# Gamepad_IO.net
KiCad netlist of a schematic drawn in Altium Designer
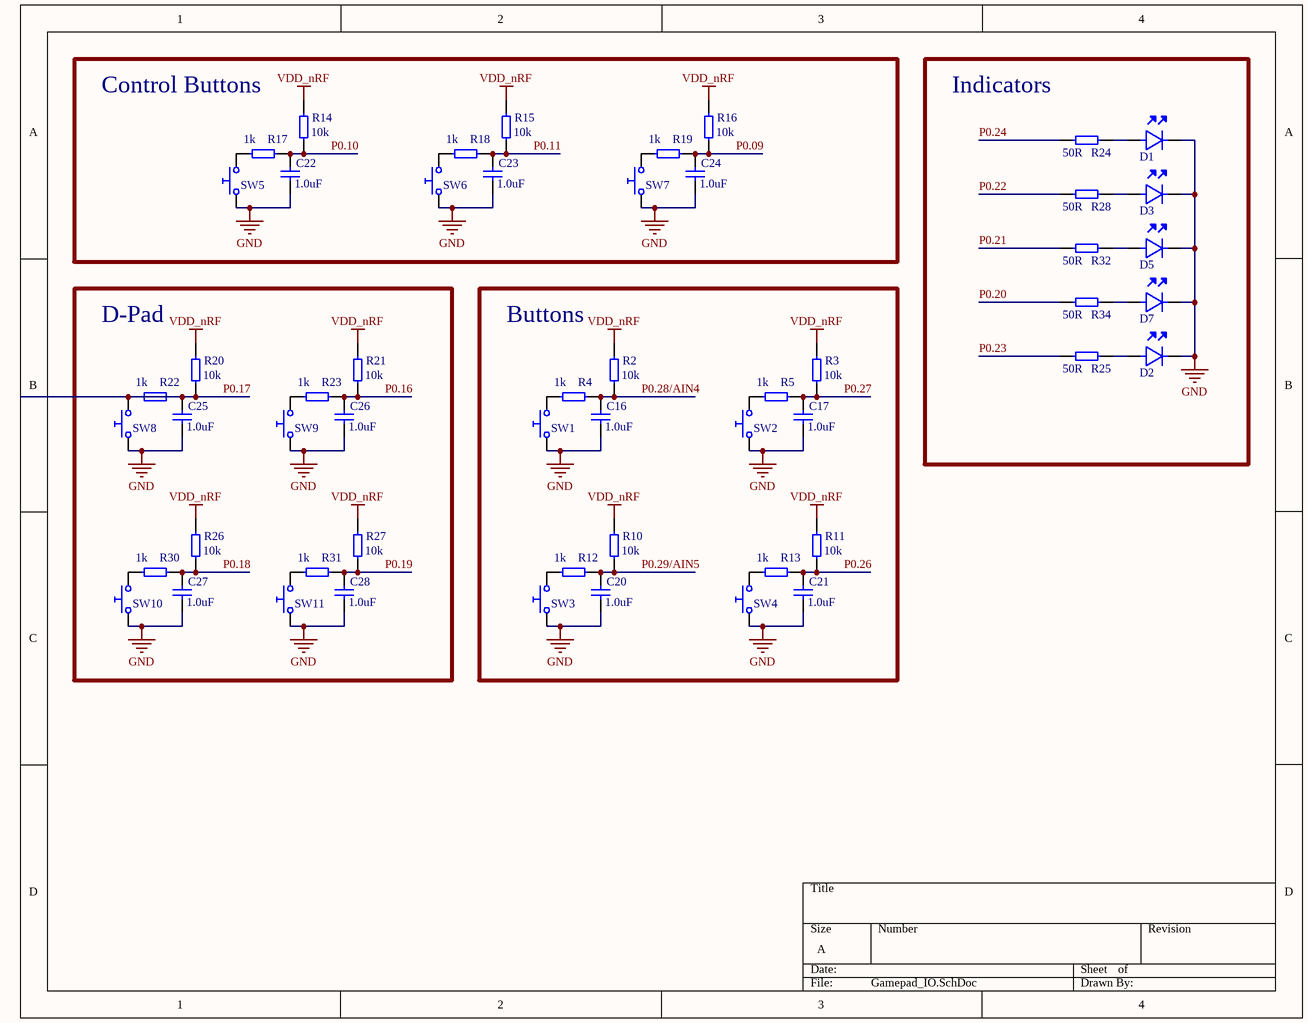
[diagram p0: Gamepad_IO.SchDoc]

(export (version "E")
  (design (tool "Eeschema 10.0.6"))
  (components
    (comp (ref "C16")
      (value "1.0uF")
      (footprint "0603 Capacitor")
      (libsource (lib "MoldsvorLibrary") (part "Capacitor"))
    )
    (comp (ref "C17")
      (value "1.0uF")
      (footprint "0603 Capacitor")
      (libsource (lib "MoldsvorLibrary") (part "Capacitor"))
    )
    (comp (ref "C20")
      (value "1.0uF")
      (footprint "0603 Capacitor")
      (libsource (lib "MoldsvorLibrary") (part "Capacitor"))
    )
    (comp (ref "C21")
      (value "1.0uF")
      (footprint "0603 Capacitor")
      (libsource (lib "MoldsvorLibrary") (part "Capacitor"))
    )
    (comp (ref "C22")
      (value "1.0uF")
      (footprint "0603 Capacitor")
      (libsource (lib "MoldsvorLibrary") (part "Capacitor"))
    )
    (comp (ref "C23")
      (value "1.0uF")
      (footprint "0603 Capacitor")
      (libsource (lib "MoldsvorLibrary") (part "Capacitor"))
    )
    (comp (ref "C24")
      (value "1.0uF")
      (footprint "0603 Capacitor")
      (libsource (lib "MoldsvorLibrary") (part "Capacitor"))
    )
    (comp (ref "C25")
      (value "1.0uF")
      (footprint "0603 Capacitor")
      (libsource (lib "MoldsvorLibrary") (part "Capacitor"))
    )
    (comp (ref "C26")
      (value "1.0uF")
      (footprint "0603 Capacitor")
      (libsource (lib "MoldsvorLibrary") (part "Capacitor"))
    )
    (comp (ref "C27")
      (value "1.0uF")
      (footprint "0603 Capacitor")
      (libsource (lib "MoldsvorLibrary") (part "Capacitor"))
    )
    (comp (ref "C28")
      (value "1.0uF")
      (footprint "0603 Capacitor")
      (libsource (lib "MoldsvorLibrary") (part "Capacitor"))
    )
    (comp (ref "D1") (value "LED") (footprint "0603 LED") (libsource (lib "MoldsvorLibrary") (part "LED")))
    (comp (ref "D2") (value "LED") (footprint "0603 LED") (libsource (lib "MoldsvorLibrary") (part "LED")))
    (comp (ref "D3") (value "LED") (footprint "0603 LED") (libsource (lib "MoldsvorLibrary") (part "LED")))
    (comp (ref "D5") (value "LED") (footprint "0603 LED") (libsource (lib "MoldsvorLibrary") (part "LED")))
    (comp (ref "D7") (value "LED") (footprint "0603 LED") (libsource (lib "MoldsvorLibrary") (part "LED")))
    (comp (ref "R2")
      (value "10k")
      (footprint "0603 Resistor")
      (libsource (lib "MoldsvorLibrary") (part "Resistor"))
    )
    (comp (ref "R3")
      (value "10k")
      (footprint "0603 Resistor")
      (libsource (lib "MoldsvorLibrary") (part "Resistor"))
    )
    (comp (ref "R4")
      (value "1k")
      (footprint "0603 Resistor")
      (libsource (lib "MoldsvorLibrary") (part "Resistor"))
    )
    (comp (ref "R5")
      (value "1k")
      (footprint "0603 Resistor")
      (libsource (lib "MoldsvorLibrary") (part "Resistor"))
    )
    (comp (ref "R10")
      (value "10k")
      (footprint "0603 Resistor")
      (libsource (lib "MoldsvorLibrary") (part "Resistor"))
    )
    (comp (ref "R11")
      (value "10k")
      (footprint "0603 Resistor")
      (libsource (lib "MoldsvorLibrary") (part "Resistor"))
    )
    (comp (ref "R12")
      (value "1k")
      (footprint "0603 Resistor")
      (libsource (lib "MoldsvorLibrary") (part "Resistor"))
    )
    (comp (ref "R13")
      (value "1k")
      (footprint "0603 Resistor")
      (libsource (lib "MoldsvorLibrary") (part "Resistor"))
    )
    (comp (ref "R14")
      (value "10k")
      (footprint "0603 Resistor")
      (libsource (lib "MoldsvorLibrary") (part "Resistor"))
    )
    (comp (ref "R15")
      (value "10k")
      (footprint "0603 Resistor")
      (libsource (lib "MoldsvorLibrary") (part "Resistor"))
    )
    (comp (ref "R16")
      (value "10k")
      (footprint "0603 Resistor")
      (libsource (lib "MoldsvorLibrary") (part "Resistor"))
    )
    (comp (ref "R17")
      (value "1k")
      (footprint "0603 Resistor")
      (libsource (lib "MoldsvorLibrary") (part "Resistor"))
    )
    (comp (ref "R18")
      (value "1k")
      (footprint "0603 Resistor")
      (libsource (lib "MoldsvorLibrary") (part "Resistor"))
    )
    (comp (ref "R19")
      (value "1k")
      (footprint "0603 Resistor")
      (libsource (lib "MoldsvorLibrary") (part "Resistor"))
    )
    (comp (ref "R20")
      (value "10k")
      (footprint "0603 Resistor")
      (libsource (lib "MoldsvorLibrary") (part "Resistor"))
    )
    (comp (ref "R21")
      (value "10k")
      (footprint "0603 Resistor")
      (libsource (lib "MoldsvorLibrary") (part "Resistor"))
    )
    (comp (ref "R22")
      (value "1k")
      (footprint "0603 Resistor")
      (libsource (lib "MoldsvorLibrary") (part "Resistor"))
    )
    (comp (ref "R23")
      (value "1k")
      (footprint "0603 Resistor")
      (libsource (lib "MoldsvorLibrary") (part "Resistor"))
    )
    (comp (ref "R24")
      (value "50R")
      (footprint "0603 Resistor")
      (libsource (lib "MoldsvorLibrary") (part "Resistor"))
    )
    (comp (ref "R25")
      (value "50R")
      (footprint "0603 Resistor")
      (libsource (lib "MoldsvorLibrary") (part "Resistor"))
    )
    (comp (ref "R26")
      (value "10k")
      (footprint "0603 Resistor")
      (libsource (lib "MoldsvorLibrary") (part "Resistor"))
    )
    (comp (ref "R27")
      (value "10k")
      (footprint "0603 Resistor")
      (libsource (lib "MoldsvorLibrary") (part "Resistor"))
    )
    (comp (ref "R28")
      (value "50R")
      (footprint "0603 Resistor")
      (libsource (lib "MoldsvorLibrary") (part "Resistor"))
    )
    (comp (ref "R30")
      (value "1k")
      (footprint "0603 Resistor")
      (libsource (lib "MoldsvorLibrary") (part "Resistor"))
    )
    (comp (ref "R31")
      (value "1k")
      (footprint "0603 Resistor")
      (libsource (lib "MoldsvorLibrary") (part "Resistor"))
    )
    (comp (ref "R32")
      (value "50R")
      (footprint "0603 Resistor")
      (libsource (lib "MoldsvorLibrary") (part "Resistor"))
    )
    (comp (ref "R34")
      (value "50R")
      (footprint "0603 Resistor")
      (libsource (lib "MoldsvorLibrary") (part "Resistor"))
    )
    (comp (ref "SW1")
      (value "Switch Button")
      (footprint "ButtonPad Version 1")
      (libsource (lib "Gamepad_Schematic_Library") (part "Switch Button"))
    )
    (comp (ref "SW2")
      (value "Switch Button")
      (footprint "ButtonPad Version 1")
      (libsource (lib "Gamepad_Schematic_Library") (part "Switch Button"))
    )
    (comp (ref "SW3")
      (value "Switch Button")
      (footprint "ButtonPad Version 1")
      (libsource (lib "Gamepad_Schematic_Library") (part "Switch Button"))
    )
    (comp (ref "SW4")
      (value "Switch Button")
      (footprint "ButtonPad Version 1")
      (libsource (lib "Gamepad_Schematic_Library") (part "Switch Button"))
    )
    (comp (ref "SW5")
      (value "Switch Button")
      (footprint "ButtonPad Version 1")
      (libsource (lib "Gamepad_Schematic_Library") (part "Switch Button"))
    )
    (comp (ref "SW6")
      (value "Switch Button")
      (footprint "ButtonPad Version 1")
      (libsource (lib "Gamepad_Schematic_Library") (part "Switch Button"))
    )
    (comp (ref "SW7")
      (value "Switch Button")
      (footprint "ButtonPad Version 1")
      (libsource (lib "Gamepad_Schematic_Library") (part "Switch Button"))
    )
    (comp (ref "SW8")
      (value "Switch Button")
      (footprint "ButtonPad Version 1")
      (libsource (lib "Gamepad_Schematic_Library") (part "Switch Button"))
    )
    (comp (ref "SW9")
      (value "Switch Button")
      (footprint "ButtonPad Version 1")
      (libsource (lib "Gamepad_Schematic_Library") (part "Switch Button"))
    )
    (comp (ref "SW10")
      (value "Switch Button")
      (footprint "ButtonPad Version 1")
      (libsource (lib "Gamepad_Schematic_Library") (part "Switch Button"))
    )
    (comp (ref "SW11")
      (value "Switch Button")
      (footprint "ButtonPad Version 1")
      (libsource (lib "Gamepad_Schematic_Library") (part "Switch Button"))
    )
  )
  (nets
    (net (code "1") (name "/P0.09") (class "Default")
      (node (ref "C24") (pin "2") (pinfunction "2_2") (pintype "passive"))
      (node (ref "R16") (pin "1") (pintype "passive"))
      (node (ref "R19") (pin "2") (pintype "passive"))
    )
    (net (code "2") (name "/P0.10") (class "Default")
      (node (ref "C22") (pin "2") (pinfunction "2_2") (pintype "passive"))
      (node (ref "R14") (pin "1") (pintype "passive"))
      (node (ref "R17") (pin "2") (pintype "passive"))
    )
    (net (code "3") (name "/P0.11") (class "Default")
      (node (ref "C23") (pin "2") (pinfunction "2_2") (pintype "passive"))
      (node (ref "R15") (pin "1") (pintype "passive"))
      (node (ref "R18") (pin "2") (pintype "passive"))
    )
    (net (code "4") (name "/P0.16") (class "Default")
      (node (ref "C26") (pin "2") (pinfunction "2_2") (pintype "passive"))
      (node (ref "R21") (pin "1") (pintype "passive"))
      (node (ref "R23") (pin "2") (pintype "passive"))
    )
    (net (code "5") (name "/P0.17") (class "Default")
      (node (ref "C25") (pin "2") (pinfunction "2_2") (pintype "passive"))
      (node (ref "R20") (pin "1") (pintype "passive"))
      (node (ref "R22") (pin "1") (pintype "passive"))
      (node (ref "R22") (pin "2") (pintype "passive"))
      (node (ref "SW8") (pin "2") (pinfunction "2_2") (pintype "passive"))
    )
    (net (code "6") (name "/P0.18") (class "Default")
      (node (ref "C27") (pin "2") (pinfunction "2_2") (pintype "passive"))
      (node (ref "R26") (pin "1") (pintype "passive"))
      (node (ref "R30") (pin "2") (pintype "passive"))
    )
    (net (code "7") (name "/P0.19") (class "Default")
      (node (ref "C28") (pin "2") (pinfunction "2_2") (pintype "passive"))
      (node (ref "R27") (pin "1") (pintype "passive"))
      (node (ref "R31") (pin "2") (pintype "passive"))
    )
    (net (code "8") (name "/P0.20") (class "Default") (node (ref "R34") (pin "1") (pintype "passive")))
    (net (code "9") (name "/P0.21") (class "Default") (node (ref "R32") (pin "1") (pintype "passive")))
    (net (code "10") (name "/P0.22") (class "Default") (node (ref "R28") (pin "1") (pintype "passive")))
    (net (code "11") (name "/P0.23") (class "Default") (node (ref "R25") (pin "1") (pintype "passive")))
    (net (code "12") (name "/P0.24") (class "Default") (node (ref "R24") (pin "1") (pintype "passive")))
    (net (code "13") (name "/P0.26") (class "Default")
      (node (ref "C21") (pin "2") (pinfunction "2_2") (pintype "passive"))
      (node (ref "R11") (pin "1") (pintype "passive"))
      (node (ref "R13") (pin "2") (pintype "passive"))
    )
    (net (code "14") (name "/P0.27") (class "Default")
      (node (ref "C17") (pin "2") (pinfunction "2_2") (pintype "passive"))
      (node (ref "R3") (pin "1") (pintype "passive"))
      (node (ref "R5") (pin "2") (pintype "passive"))
    )
    (net (code "15") (name "/P0.28{slash}AIN4") (class "Default")
      (node (ref "C16") (pin "2") (pinfunction "2_2") (pintype "passive"))
      (node (ref "R2") (pin "1") (pintype "passive"))
      (node (ref "R4") (pin "2") (pintype "passive"))
    )
    (net (code "16") (name "/P0.29{slash}AIN5") (class "Default")
      (node (ref "C20") (pin "2") (pinfunction "2_2") (pintype "passive"))
      (node (ref "R10") (pin "1") (pintype "passive"))
      (node (ref "R12") (pin "2") (pintype "passive"))
    )
    (net (code "17") (name "GND") (class "Default")
      (node (ref "C16") (pin "1") (pinfunction "1_1") (pintype "passive"))
      (node (ref "C17") (pin "1") (pinfunction "1_1") (pintype "passive"))
      (node (ref "C20") (pin "1") (pinfunction "1_1") (pintype "passive"))
      (node (ref "C21") (pin "1") (pinfunction "1_1") (pintype "passive"))
      (node (ref "C22") (pin "1") (pinfunction "1_1") (pintype "passive"))
      (node (ref "C23") (pin "1") (pinfunction "1_1") (pintype "passive"))
      (node (ref "C24") (pin "1") (pinfunction "1_1") (pintype "passive"))
      (node (ref "C25") (pin "1") (pinfunction "1_1") (pintype "passive"))
      (node (ref "C26") (pin "1") (pinfunction "1_1") (pintype "passive"))
      (node (ref "C27") (pin "1") (pinfunction "1_1") (pintype "passive"))
      (node (ref "C28") (pin "1") (pinfunction "1_1") (pintype "passive"))
      (node (ref "D1") (pin "2") (pintype "passive"))
      (node (ref "D2") (pin "2") (pintype "passive"))
      (node (ref "D3") (pin "2") (pintype "passive"))
      (node (ref "D5") (pin "2") (pintype "passive"))
      (node (ref "D7") (pin "2") (pintype "passive"))
      (node (ref "SW1") (pin "1") (pinfunction "1_1") (pintype "passive"))
      (node (ref "SW10") (pin "1") (pinfunction "1_1") (pintype "passive"))
      (node (ref "SW11") (pin "1") (pinfunction "1_1") (pintype "passive"))
      (node (ref "SW2") (pin "1") (pinfunction "1_1") (pintype "passive"))
      (node (ref "SW3") (pin "1") (pinfunction "1_1") (pintype "passive"))
      (node (ref "SW4") (pin "1") (pinfunction "1_1") (pintype "passive"))
      (node (ref "SW5") (pin "1") (pinfunction "1_1") (pintype "passive"))
      (node (ref "SW6") (pin "1") (pinfunction "1_1") (pintype "passive"))
      (node (ref "SW7") (pin "1") (pinfunction "1_1") (pintype "passive"))
      (node (ref "SW8") (pin "1") (pinfunction "1_1") (pintype "passive"))
      (node (ref "SW9") (pin "1") (pinfunction "1_1") (pintype "passive"))
    )
    (net (code "18") (name "Net-(D1-Pad1)") (class "Default")
      (node (ref "D1") (pin "1") (pintype "passive"))
      (node (ref "R24") (pin "2") (pintype "passive"))
    )
    (net (code "19") (name "Net-(D2-Pad1)") (class "Default")
      (node (ref "D2") (pin "1") (pintype "passive"))
      (node (ref "R25") (pin "2") (pintype "passive"))
    )
    (net (code "20") (name "Net-(D3-Pad1)") (class "Default")
      (node (ref "D3") (pin "1") (pintype "passive"))
      (node (ref "R28") (pin "2") (pintype "passive"))
    )
    (net (code "21") (name "Net-(D5-Pad1)") (class "Default")
      (node (ref "D5") (pin "1") (pintype "passive"))
      (node (ref "R32") (pin "2") (pintype "passive"))
    )
    (net (code "22") (name "Net-(D7-Pad1)") (class "Default")
      (node (ref "D7") (pin "1") (pintype "passive"))
      (node (ref "R34") (pin "2") (pintype "passive"))
    )
    (net (code "23") (name "Net-(R4-Pad1)") (class "Default")
      (node (ref "R4") (pin "1") (pintype "passive"))
      (node (ref "SW1") (pin "2") (pinfunction "2_2") (pintype "passive"))
    )
    (net (code "24") (name "Net-(R5-Pad1)") (class "Default")
      (node (ref "R5") (pin "1") (pintype "passive"))
      (node (ref "SW2") (pin "2") (pinfunction "2_2") (pintype "passive"))
    )
    (net (code "25") (name "Net-(R12-Pad1)") (class "Default")
      (node (ref "R12") (pin "1") (pintype "passive"))
      (node (ref "SW3") (pin "2") (pinfunction "2_2") (pintype "passive"))
    )
    (net (code "26") (name "Net-(R13-Pad1)") (class "Default")
      (node (ref "R13") (pin "1") (pintype "passive"))
      (node (ref "SW4") (pin "2") (pinfunction "2_2") (pintype "passive"))
    )
    (net (code "27") (name "Net-(R17-Pad1)") (class "Default")
      (node (ref "R17") (pin "1") (pintype "passive"))
      (node (ref "SW5") (pin "2") (pinfunction "2_2") (pintype "passive"))
    )
    (net (code "28") (name "Net-(R18-Pad1)") (class "Default")
      (node (ref "R18") (pin "1") (pintype "passive"))
      (node (ref "SW6") (pin "2") (pinfunction "2_2") (pintype "passive"))
    )
    (net (code "29") (name "Net-(R19-Pad1)") (class "Default")
      (node (ref "R19") (pin "1") (pintype "passive"))
      (node (ref "SW7") (pin "2") (pinfunction "2_2") (pintype "passive"))
    )
    (net (code "30") (name "Net-(R23-Pad1)") (class "Default")
      (node (ref "R23") (pin "1") (pintype "passive"))
      (node (ref "SW9") (pin "2") (pinfunction "2_2") (pintype "passive"))
    )
    (net (code "31") (name "Net-(R30-Pad1)") (class "Default")
      (node (ref "R30") (pin "1") (pintype "passive"))
      (node (ref "SW10") (pin "2") (pinfunction "2_2") (pintype "passive"))
    )
    (net (code "32") (name "Net-(R31-Pad1)") (class "Default")
      (node (ref "R31") (pin "1") (pintype "passive"))
      (node (ref "SW11") (pin "2") (pinfunction "2_2") (pintype "passive"))
    )
    (net (code "33") (name "VDD_nRF") (class "Default")
      (node (ref "R10") (pin "2") (pintype "passive"))
      (node (ref "R11") (pin "2") (pintype "passive"))
      (node (ref "R14") (pin "2") (pintype "passive"))
      (node (ref "R15") (pin "2") (pintype "passive"))
      (node (ref "R16") (pin "2") (pintype "passive"))
      (node (ref "R2") (pin "2") (pintype "passive"))
      (node (ref "R20") (pin "2") (pintype "passive"))
      (node (ref "R21") (pin "2") (pintype "passive"))
      (node (ref "R26") (pin "2") (pintype "passive"))
      (node (ref "R27") (pin "2") (pintype "passive"))
      (node (ref "R3") (pin "2") (pintype "passive"))
    )
  )
)
